# vector-06-easyeda.net
KiCad netlist of a schematic drawn in EasyEDA Pro
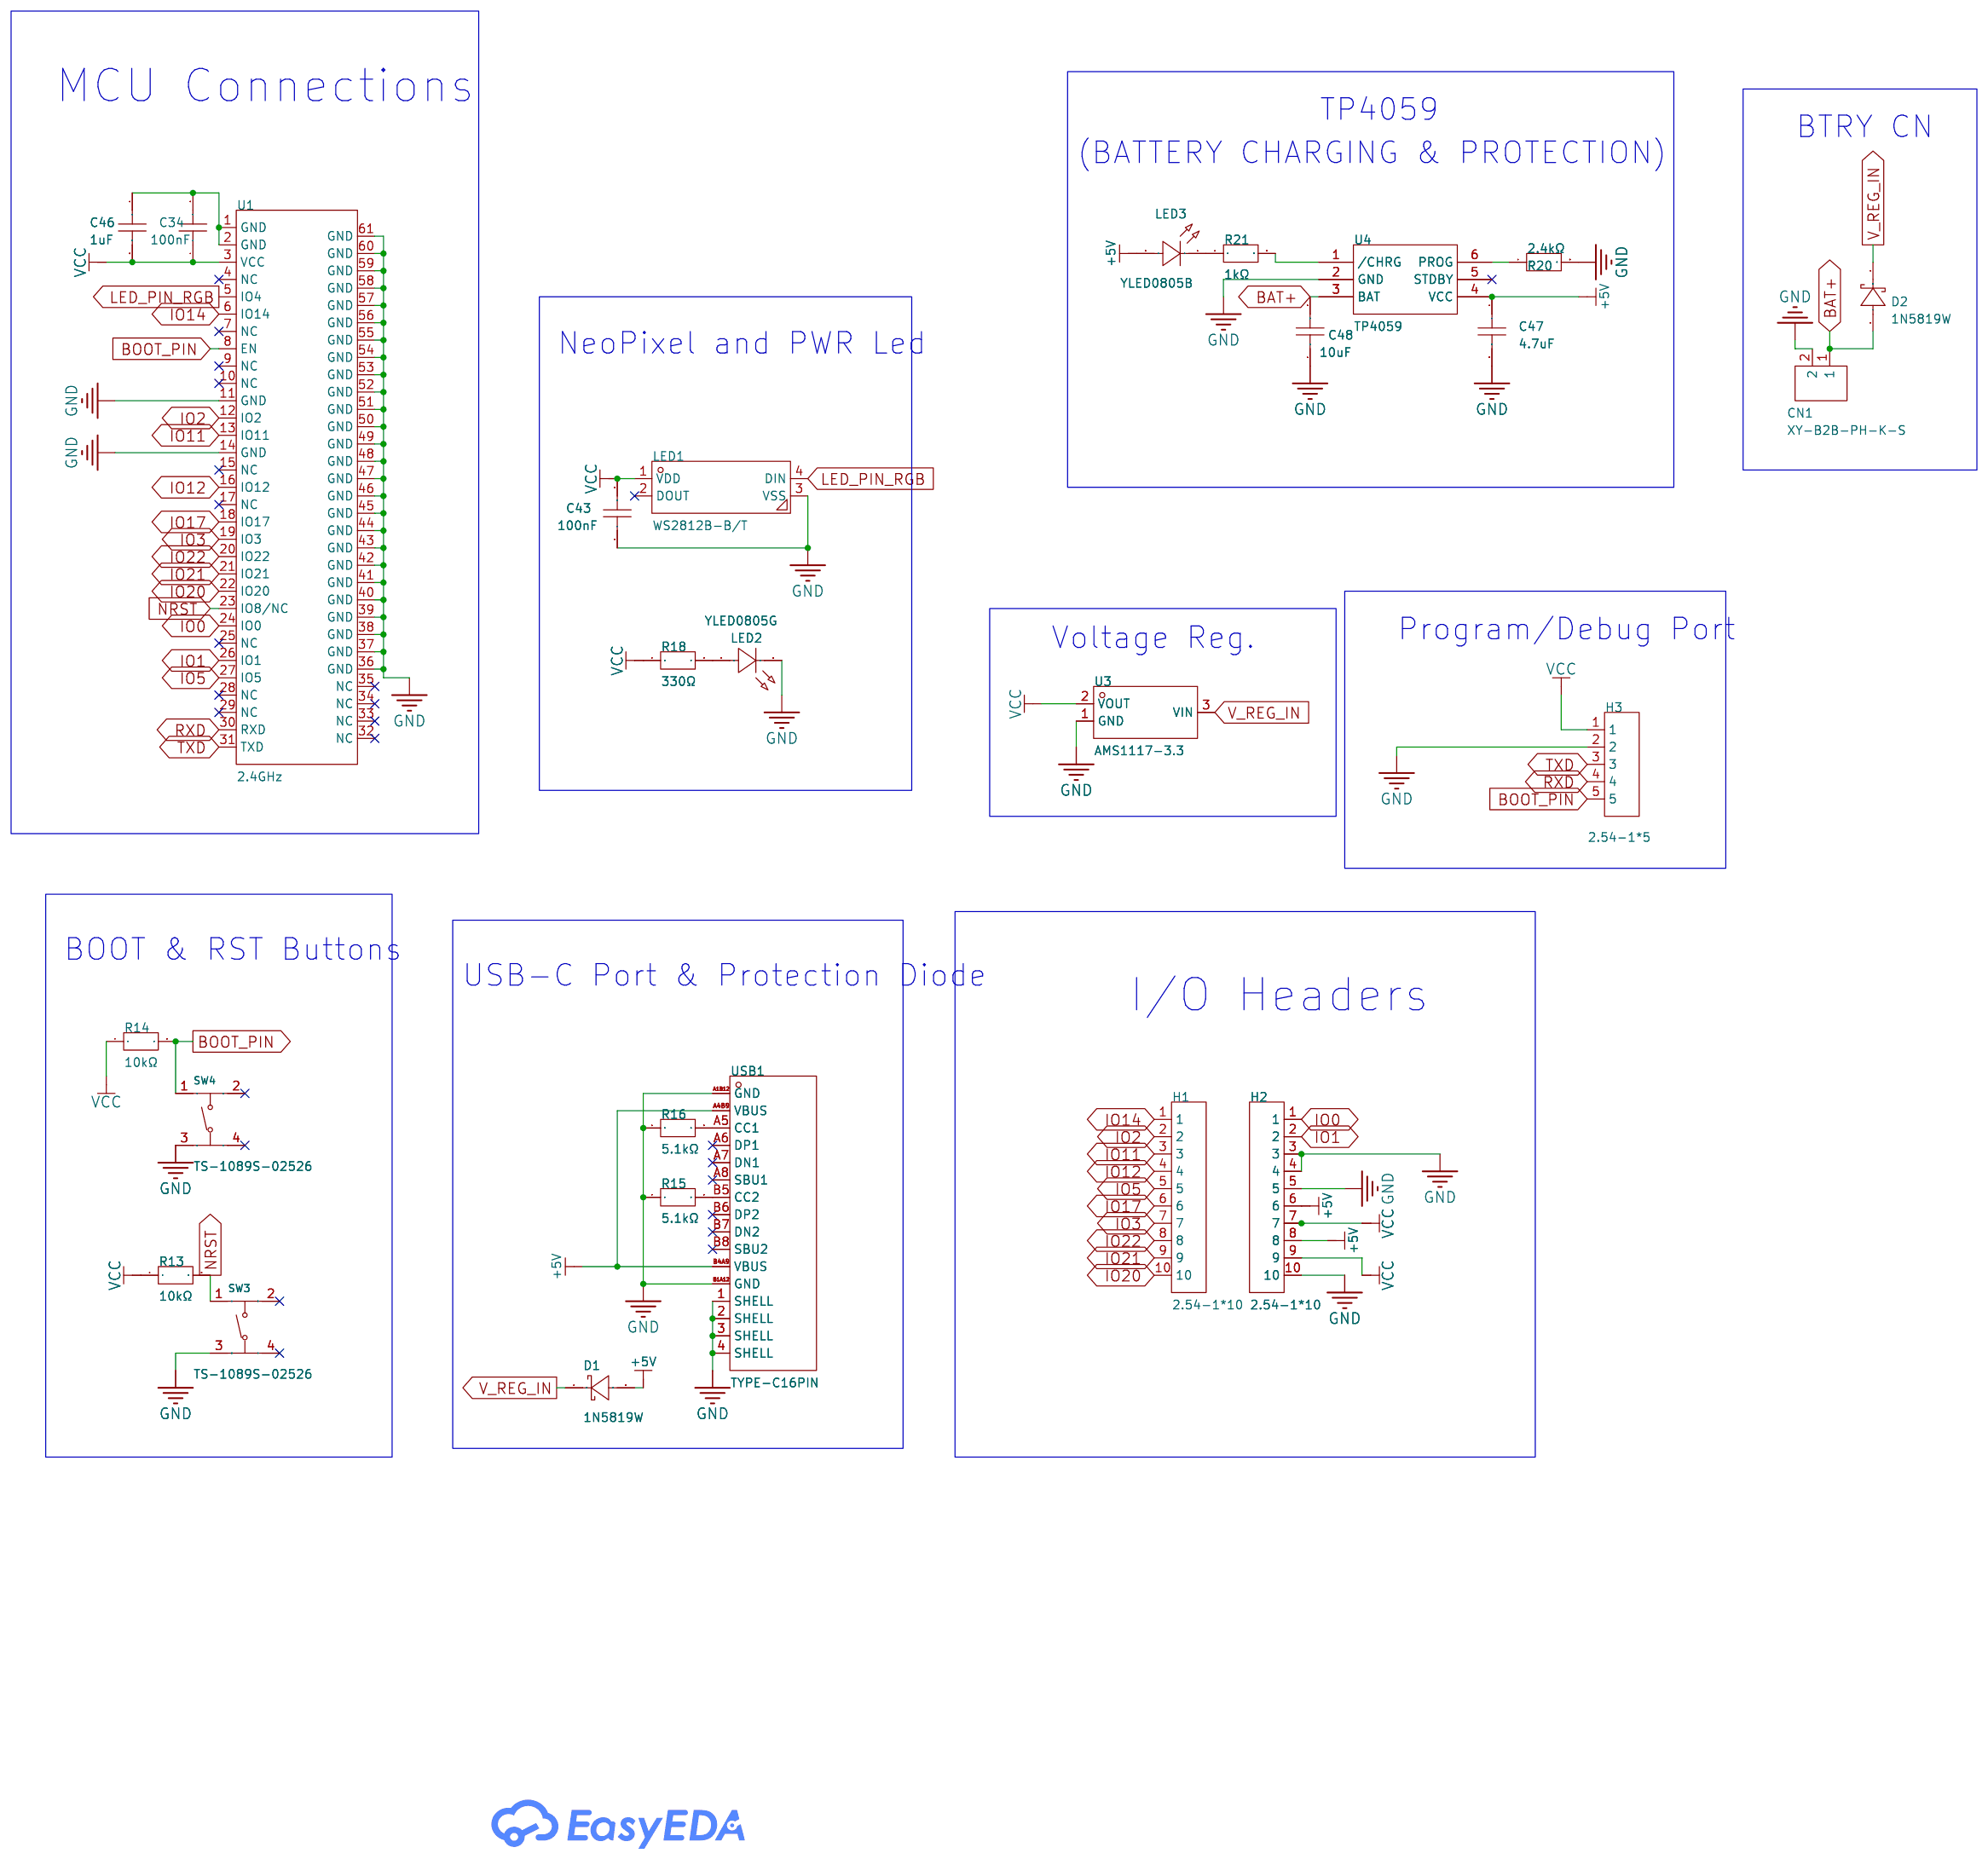
[diagram p0: schematic sheet]

(export (version "E")
  (design (tool "Eeschema 10.0.6"))
  (components
    (comp (ref "C34")
      (value "100nF")
      (footprint "easyedapro:C0603")
      (description "Capacitance:100nF Tolerance:±10% Tolerance:±10% Voltage Rating:50V Temperature Coefficient:X7R")
      (fields
        (field (name "Manufacturer Part") "FCC0603B104K500CT")
        (field (name "Manufacturer") "FOJAN(富捷)")
      )
      (libsource (lib "easyedapro") (part "FCC0603B104K500CT"))
    )
    (comp (ref "C43")
      (value "100nF")
      (footprint "easyedapro:C0603")
      (description "Capacitance:100nF Tolerance:±10% Tolerance:±10% Voltage Rating:50V Temperature Coefficient:X7R")
      (fields
        (field (name "Manufacturer Part") "FCC0603B104K500CT")
        (field (name "Manufacturer") "FOJAN(富捷)")
      )
      (libsource (lib "easyedapro") (part "FCC0603B104K500CT"))
    )
    (comp (ref "C46")
      (value "1uF")
      (footprint "easyedapro:C0603")
      (description "Capacitance:1uF Tolerance:±10% Tolerance:±10% Voltage Rating:50V Temperature Coefficient:X5R")
      (fields
        (field (name "Manufacturer Part") "CGA0603X5R105K500JT")
        (field (name "Manufacturer") "HRE(芯声)")
      )
      (libsource (lib "easyedapro") (part "CGA0603X5R105K500JT"))
    )
    (comp (ref "C47")
      (value "4.7uF")
      (footprint "easyedapro:C0603")
      (description "Capacitance:4.7uF Tolerance:±10% Tolerance:±10% Voltage Rating:16V Temperature Coefficient:X5R")
      (fields
        (field (name "Manufacturer Part") "TCC0603X5R475K160CT")
        (field (name "Manufacturer") "CCTC(三环)")
      )
      (libsource (lib "easyedapro") (part "TCC0603X5R475K160CT"))
    )
    (comp (ref "C48")
      (value "10uF")
      (footprint "easyedapro:C0603")
      (description "Capacitance:10uF Tolerance:±10% Tolerance:±10% Voltage Rating:10V Temperature Coefficient:X5R")
      (fields
        (field (name "Manufacturer Part") "TCC0603X5R106K100CT")
        (field (name "Manufacturer") "CCTC(三环)")
      )
      (libsource (lib "easyedapro") (part "TCC0603X5R106K100CT"))
    )
    (comp (ref "CN1")
      (value "XY-B2B-PH-K-S")
      (footprint "easyedapro:CONN-TH_B2B-PH-K-S")
      (fields (field (name "Manufacturer") "XYECONN(辛译)"))
      (libsource (lib "easyedapro") (part "XY-B2B-PH-K-S"))
    )
    (comp (ref "D1")
      (value "1N5819W")
      (footprint "easyedapro:SOD-123_L2.7-W1.6-LS3.7-RD")
      (fields (field (name "Manufacturer") "GOODWORK(固得沃克)"))
      (libsource (lib "easyedapro") (part "1N5819W_C41431973"))
    )
    (comp (ref "D2")
      (value "1N5819W")
      (footprint "easyedapro:SOD-123_L2.7-W1.6-LS3.7-RD")
      (fields (field (name "Manufacturer") "GOODWORK(固得沃克)"))
      (libsource (lib "easyedapro") (part "1N5819W_C41431973"))
    )
    (comp (ref "H1")
      (value "2.54-1*10")
      (footprint "easyedapro:HDR-TH_10P-P2.54-V-M")
      (fields (field (name "Manufacturer") "ZHOURI(洲日)"))
      (libsource (lib "easyedapro") (part "2.54-1*10"))
    )
    (comp (ref "H2")
      (value "2.54-1*10")
      (footprint "easyedapro:HDR-TH_10P-P2.54-V-M")
      (fields (field (name "Manufacturer") "ZHOURI(洲日)"))
      (libsource (lib "easyedapro") (part "2.54-1*10"))
    )
    (comp (ref "H3")
      (value "2.54-1*5")
      (footprint "easyedapro:HDR-TH_5P-P2.54-V-M")
      (fields (field (name "Manufacturer") "ZHOURI(洲日)"))
      (libsource (lib "easyedapro") (part "2.54-1*5"))
    )
    (comp (ref "LED1")
      (value "WS2812B-B/T")
      (footprint "easyedapro:LED-SMD_4P-L5.0-W5.0-TL_WS2812B-B")
      (fields (field (name "Manufacturer") "worldsemi"))
      (libsource (lib "easyedapro") (part "WS2812B-B/W"))
    )
    (comp (ref "LED2")
      (value "YLED0805G")
      (footprint "easyedapro:LED0805-FD-GREEN")
      (fields (field (name "Manufacturer") "YONGYUTAI(永裕泰)"))
      (libsource (lib "easyedapro") (part "YLED0805G"))
    )
    (comp (ref "LED3")
      (value "YLED0805B")
      (footprint "easyedapro:LED0805-RD")
      (fields (field (name "Manufacturer") "YONGYUTAI(永裕泰)"))
      (libsource (lib "easyedapro") (part "YLED0805B"))
    )
    (comp (ref "R13")
      (value "10kΩ")
      (footprint "easyedapro:R0603")
      (fields (field (name "Manufacturer Part") "FRC0603J103 TS") (field (name "Manufacturer") "FOJAN(富捷)"))
      (libsource (lib "easyedapro") (part "FRC0603J103TS"))
    )
    (comp (ref "R14")
      (value "10kΩ")
      (footprint "easyedapro:R0603")
      (fields (field (name "Manufacturer Part") "FRC0603J103 TS") (field (name "Manufacturer") "FOJAN(富捷)"))
      (libsource (lib "easyedapro") (part "FRC0603J103TS"))
    )
    (comp (ref "R15")
      (value "5.1kΩ")
      (footprint "easyedapro:R0603")
      (fields (field (name "Manufacturer Part") "FRC0603F5101TS") (field (name "Manufacturer") "FOJAN(富捷)"))
      (libsource (lib "easyedapro") (part "FRC0603F5101TS"))
    )
    (comp (ref "R16")
      (value "5.1kΩ")
      (footprint "easyedapro:R0603")
      (fields (field (name "Manufacturer Part") "FRC0603F5101TS") (field (name "Manufacturer") "FOJAN(富捷)"))
      (libsource (lib "easyedapro") (part "FRC0603F5101TS"))
    )
    (comp (ref "R18")
      (value "330Ω")
      (footprint "easyedapro:R0603")
      (fields (field (name "Manufacturer Part") "FRC0603J331 TS") (field (name "Manufacturer") "FOJAN(富捷)"))
      (libsource (lib "easyedapro") (part "FRC0603J331 TS"))
    )
    (comp (ref "R20")
      (value "2.4kΩ")
      (footprint "easyedapro:R0603")
      (fields (field (name "Manufacturer Part") "FRC0603F2401TS") (field (name "Manufacturer") "FOJAN(富捷)"))
      (libsource (lib "easyedapro") (part "FRC0603F2401TS"))
    )
    (comp (ref "R21")
      (value "1kΩ")
      (footprint "easyedapro:R0603")
      (fields (field (name "Manufacturer Part") "FRC0603J102 TS") (field (name "Manufacturer") "FOJAN(富捷)"))
      (libsource (lib "easyedapro") (part "FRC0603J102 TS"))
    )
    (comp (ref "SW3")
      (value "TS-1089S-02526")
      (footprint "easyedapro:SW-SMD_4P-L4.2-W3.3-P2.15-LS5.1")
      (fields (field (name "Manufacturer") "XUNPU(讯普)"))
      (libsource (lib "easyedapro") (part "TS-1089S-02526"))
    )
    (comp (ref "SW4")
      (value "TS-1089S-02526")
      (footprint "easyedapro:SW-SMD_4P-L4.2-W3.3-P2.15-LS5.1")
      (fields (field (name "Manufacturer") "XUNPU(讯普)"))
      (libsource (lib "easyedapro") (part "TS-1089S-02526"))
    )
    (comp (ref "U1")
      (value "2.4GHz")
      (footprint "easyedapro:WIFIM-SMD_61P-L13.2-W12.5-P0.80")
      (fields
        (field (name "Manufacturer Part") "Ai-WB2-M1-I")
        (field (name "Manufacturer") "Ai-Thinker(安信可)")
      )
      (libsource (lib "easyedapro") (part "AI-WB2-M1-I"))
    )
    (comp (ref "U3")
      (value "AMS1117-3.3")
      (footprint "easyedapro:SOT-223-3_L6.5-W3.4-P2.30-LS7.0-BR-1")
      (fields (field (name "Manufacturer") "晶扬电子"))
      (libsource (lib "easyedapro") (part "AMS1117-3.3_C22459274"))
    )
    (comp (ref "U4")
      (value "TP4059")
      (footprint "easyedapro:SOT-23-6_L2.9-W1.6-P0.95-LS2.8-BR")
      (fields (field (name "Manufacturer") "TOPPOWER(南京拓微)"))
      (libsource (lib "easyedapro") (part "TP4059"))
    )
    (comp (ref "USB1")
      (value "TYPE-C16PIN")
      (footprint "easyedapro:USB-C-SMD_TYPE-C16PIN")
      (fields (field (name "Manufacturer") "SHOU HAN(首韩)"))
      (libsource (lib "easyedapro") (part "TYPE-C16PIN"))
    )
  )
  (nets
    (net (code "1") (name "+5V") (class "Default")
      (node (ref "C47") (pin "1") (pinfunction "1_1") (pintype "unspecified"))
      (node (ref "D1") (pin "2") (pinfunction "A_2") (pintype "unspecified"))
      (node (ref "H2") (pin "6") (pinfunction "6_6") (pintype "unspecified"))
      (node (ref "H2") (pin "8") (pinfunction "8_8") (pintype "unspecified"))
      (node (ref "LED3") (pin "2") (pinfunction "A_2") (pintype "unspecified"))
      (node (ref "U4") (pin "4") (pinfunction "VCC_4") (pintype "unspecified"))
      (node (ref "USB1") (pin "A4B9") (pinfunction "VBUS_A4B9") (pintype "unspecified"))
      (node (ref "USB1") (pin "B4A9") (pinfunction "VBUS_B4A9") (pintype "unspecified"))
    )
    (net (code "2") (name "BAT+") (class "Default")
      (node (ref "C48") (pin "2") (pinfunction "2_2") (pintype "unspecified"))
      (node (ref "CN1") (pin "1") (pinfunction "1_1") (pintype "unspecified"))
      (node (ref "D2") (pin "2") (pinfunction "A_2") (pintype "unspecified"))
      (node (ref "U4") (pin "3") (pinfunction "BAT_3") (pintype "unspecified"))
    )
    (net (code "3") (name "BOOT_PIN") (class "Default")
      (node (ref "H3") (pin "5") (pinfunction "5_5") (pintype "unspecified"))
      (node (ref "R14") (pin "2") (pinfunction "2_2") (pintype "unspecified"))
      (node (ref "SW4") (pin "1") (pinfunction "1_1") (pintype "input"))
      (node (ref "U1") (pin "8") (pinfunction "EN_8") (pintype "unspecified"))
    )
    (net (code "4") (name "GND") (class "Default")
      (node (ref "C43") (pin "1") (pinfunction "1_1") (pintype "unspecified"))
      (node (ref "C47") (pin "2") (pinfunction "2_2") (pintype "unspecified"))
      (node (ref "C48") (pin "1") (pinfunction "1_1") (pintype "unspecified"))
      (node (ref "CN1") (pin "2") (pinfunction "2_2") (pintype "unspecified"))
      (node (ref "H2") (pin "10") (pinfunction "10_10") (pintype "unspecified"))
      (node (ref "H2") (pin "3") (pinfunction "3_3") (pintype "unspecified"))
      (node (ref "H2") (pin "4") (pinfunction "4_4") (pintype "unspecified"))
      (node (ref "H2") (pin "5") (pinfunction "5_5") (pintype "unspecified"))
      (node (ref "H3") (pin "2") (pinfunction "2_2") (pintype "unspecified"))
      (node (ref "LED1") (pin "3") (pinfunction "VSS_3") (pintype "unspecified"))
      (node (ref "LED2") (pin "2") (pinfunction "K_2") (pintype "unspecified"))
      (node (ref "R15") (pin "1") (pinfunction "1_1") (pintype "unspecified"))
      (node (ref "R16") (pin "1") (pinfunction "1_1") (pintype "unspecified"))
      (node (ref "R20") (pin "2") (pinfunction "2_2") (pintype "unspecified"))
      (node (ref "SW3") (pin "3") (pinfunction "3_3") (pintype "input"))
      (node (ref "SW4") (pin "3") (pinfunction "3_3") (pintype "input"))
      (node (ref "U1") (pin "11") (pinfunction "GND_11") (pintype "unspecified"))
      (node (ref "U1") (pin "14") (pinfunction "GND_14") (pintype "unspecified"))
      (node (ref "U1") (pin "36") (pinfunction "GND_36") (pintype "unspecified"))
      (node (ref "U1") (pin "37") (pinfunction "GND_37") (pintype "unspecified"))
      (node (ref "U1") (pin "38") (pinfunction "GND_38") (pintype "unspecified"))
      (node (ref "U1") (pin "39") (pinfunction "GND_39") (pintype "unspecified"))
      (node (ref "U1") (pin "40") (pinfunction "GND_40") (pintype "unspecified"))
      (node (ref "U1") (pin "41") (pinfunction "GND_41") (pintype "unspecified"))
      (node (ref "U1") (pin "42") (pinfunction "GND_42") (pintype "unspecified"))
      (node (ref "U1") (pin "43") (pinfunction "GND_43") (pintype "unspecified"))
      (node (ref "U1") (pin "44") (pinfunction "GND_44") (pintype "unspecified"))
      (node (ref "U1") (pin "45") (pinfunction "GND_45") (pintype "unspecified"))
      (node (ref "U1") (pin "46") (pinfunction "GND_46") (pintype "unspecified"))
      (node (ref "U1") (pin "47") (pinfunction "GND_47") (pintype "unspecified"))
      (node (ref "U1") (pin "48") (pinfunction "GND_48") (pintype "unspecified"))
      (node (ref "U1") (pin "49") (pinfunction "GND_49") (pintype "unspecified"))
      (node (ref "U1") (pin "50") (pinfunction "GND_50") (pintype "unspecified"))
      (node (ref "U1") (pin "51") (pinfunction "GND_51") (pintype "unspecified"))
      (node (ref "U1") (pin "52") (pinfunction "GND_52") (pintype "unspecified"))
      (node (ref "U1") (pin "53") (pinfunction "GND_53") (pintype "unspecified"))
      (node (ref "U1") (pin "54") (pinfunction "GND_54") (pintype "unspecified"))
      (node (ref "U1") (pin "55") (pinfunction "GND_55") (pintype "unspecified"))
      (node (ref "U1") (pin "56") (pinfunction "GND_56") (pintype "unspecified"))
      (node (ref "U1") (pin "57") (pinfunction "GND_57") (pintype "unspecified"))
      (node (ref "U1") (pin "58") (pinfunction "GND_58") (pintype "unspecified"))
      (node (ref "U1") (pin "59") (pinfunction "GND_59") (pintype "unspecified"))
      (node (ref "U1") (pin "60") (pinfunction "GND_60") (pintype "unspecified"))
      (node (ref "U1") (pin "61") (pinfunction "GND_61") (pintype "unspecified"))
      (node (ref "U3") (pin "1") (pinfunction "GND_1") (pintype "unspecified"))
      (node (ref "U4") (pin "2") (pinfunction "GND_2") (pintype "unspecified"))
      (node (ref "USB1") (pin "1") (pinfunction "SHELL_1") (pintype "unspecified"))
      (node (ref "USB1") (pin "2") (pinfunction "SHELL_2") (pintype "unspecified"))
      (node (ref "USB1") (pin "3") (pinfunction "SHELL_3") (pintype "unspecified"))
      (node (ref "USB1") (pin "4") (pinfunction "SHELL_4") (pintype "unspecified"))
      (node (ref "USB1") (pin "A1B12") (pinfunction "GND_A1B12") (pintype "unspecified"))
      (node (ref "USB1") (pin "B1A12") (pinfunction "GND_B1A12") (pintype "unspecified"))
    )
    (net (code "5") (name "IO0") (class "Default")
      (node (ref "H2") (pin "1") (pinfunction "1_1") (pintype "unspecified"))
      (node (ref "U1") (pin "24") (pinfunction "IO0_24") (pintype "unspecified"))
    )
    (net (code "6") (name "IO1") (class "Default")
      (node (ref "H2") (pin "2") (pinfunction "2_2") (pintype "unspecified"))
      (node (ref "U1") (pin "26") (pinfunction "IO1_26") (pintype "unspecified"))
    )
    (net (code "7") (name "IO2") (class "Default")
      (node (ref "H1") (pin "2") (pinfunction "2_2") (pintype "unspecified"))
      (node (ref "U1") (pin "12") (pinfunction "IO2_12") (pintype "unspecified"))
    )
    (net (code "8") (name "IO3") (class "Default")
      (node (ref "H1") (pin "7") (pinfunction "7_7") (pintype "unspecified"))
      (node (ref "U1") (pin "19") (pinfunction "IO3_19") (pintype "unspecified"))
    )
    (net (code "9") (name "IO5") (class "Default")
      (node (ref "H1") (pin "5") (pinfunction "5_5") (pintype "unspecified"))
      (node (ref "U1") (pin "27") (pinfunction "IO5_27") (pintype "unspecified"))
    )
    (net (code "10") (name "IO11") (class "Default")
      (node (ref "H1") (pin "3") (pinfunction "3_3") (pintype "unspecified"))
      (node (ref "U1") (pin "13") (pinfunction "IO11_13") (pintype "unspecified"))
    )
    (net (code "11") (name "IO12") (class "Default")
      (node (ref "H1") (pin "4") (pinfunction "4_4") (pintype "unspecified"))
      (node (ref "U1") (pin "16") (pinfunction "IO12_16") (pintype "unspecified"))
    )
    (net (code "12") (name "IO14") (class "Default")
      (node (ref "H1") (pin "1") (pinfunction "1_1") (pintype "unspecified"))
      (node (ref "U1") (pin "6") (pinfunction "IO14_6") (pintype "unspecified"))
    )
    (net (code "13") (name "IO17") (class "Default")
      (node (ref "H1") (pin "6") (pinfunction "6_6") (pintype "unspecified"))
      (node (ref "U1") (pin "18") (pinfunction "IO17_18") (pintype "unspecified"))
    )
    (net (code "14") (name "IO20") (class "Default")
      (node (ref "H1") (pin "10") (pinfunction "10_10") (pintype "unspecified"))
      (node (ref "U1") (pin "22") (pinfunction "IO20_22") (pintype "unspecified"))
    )
    (net (code "15") (name "IO21") (class "Default")
      (node (ref "H1") (pin "9") (pinfunction "9_9") (pintype "unspecified"))
      (node (ref "U1") (pin "21") (pinfunction "IO21_21") (pintype "unspecified"))
    )
    (net (code "16") (name "IO22") (class "Default")
      (node (ref "H1") (pin "8") (pinfunction "8_8") (pintype "unspecified"))
      (node (ref "U1") (pin "20") (pinfunction "IO22_20") (pintype "unspecified"))
    )
    (net (code "17") (name "LED_PIN_RGB") (class "Default")
      (node (ref "LED1") (pin "4") (pinfunction "DIN_4") (pintype "unspecified"))
      (node (ref "U1") (pin "5") (pinfunction "IO4_5") (pintype "unspecified"))
    )
    (net (code "18") (name "NRST") (class "Default")
      (node (ref "R13") (pin "2") (pinfunction "2_2") (pintype "unspecified"))
      (node (ref "SW3") (pin "1") (pinfunction "1_1") (pintype "input"))
      (node (ref "U1") (pin "23") (pinfunction "IO8/NC_23") (pintype "unspecified"))
    )
    (net (code "19") (name "Net-(C34-Pad2)") (class "Default")
      (node (ref "C34") (pin "2") (pinfunction "2_2") (pintype "unspecified"))
      (node (ref "C46") (pin "1") (pinfunction "1_1") (pintype "unspecified"))
      (node (ref "U1") (pin "1") (pinfunction "GND_1") (pintype "unspecified"))
      (node (ref "U1") (pin "2") (pinfunction "GND_2") (pintype "unspecified"))
    )
    (net (code "20") (name "Net-(LED2-A)") (class "Default")
      (node (ref "LED2") (pin "1") (pinfunction "A_1") (pintype "unspecified"))
      (node (ref "R18") (pin "2") (pinfunction "2_2") (pintype "unspecified"))
    )
    (net (code "21") (name "Net-(LED3-K)") (class "Default")
      (node (ref "LED3") (pin "1") (pinfunction "K_1") (pintype "unspecified"))
      (node (ref "R21") (pin "1") (pinfunction "1_1") (pintype "unspecified"))
    )
    (net (code "22") (name "Net-(U4-PROG)") (class "Default")
      (node (ref "R20") (pin "1") (pinfunction "1_1") (pintype "unspecified"))
      (node (ref "U4") (pin "6") (pinfunction "PROG_6") (pintype "unspecified"))
    )
    (net (code "23") (name "Net-(U4-{slash}CHRG)") (class "Default")
      (node (ref "R21") (pin "2") (pinfunction "2_2") (pintype "unspecified"))
      (node (ref "U4") (pin "1") (pinfunction "/CHRG_1") (pintype "unspecified"))
    )
    (net (code "24") (name "Net-(USB1-CC1)") (class "Default")
      (node (ref "R16") (pin "2") (pinfunction "2_2") (pintype "unspecified"))
      (node (ref "USB1") (pin "A5") (pinfunction "CC1_A5") (pintype "unspecified"))
    )
    (net (code "25") (name "Net-(USB1-CC2)") (class "Default")
      (node (ref "R15") (pin "2") (pinfunction "2_2") (pintype "unspecified"))
      (node (ref "USB1") (pin "B5") (pinfunction "CC2_B5") (pintype "unspecified"))
    )
    (net (code "26") (name "RXD") (class "Default")
      (node (ref "H3") (pin "4") (pinfunction "4_4") (pintype "unspecified"))
      (node (ref "U1") (pin "30") (pinfunction "RXD_30") (pintype "unspecified"))
    )
    (net (code "27") (name "TXD") (class "Default")
      (node (ref "H3") (pin "3") (pinfunction "3_3") (pintype "unspecified"))
      (node (ref "U1") (pin "31") (pinfunction "TXD_31") (pintype "unspecified"))
    )
    (net (code "28") (name "VCC") (class "Default")
      (node (ref "C34") (pin "1") (pinfunction "1_1") (pintype "unspecified"))
      (node (ref "C43") (pin "2") (pinfunction "2_2") (pintype "unspecified"))
      (node (ref "C46") (pin "2") (pinfunction "2_2") (pintype "unspecified"))
      (node (ref "H2") (pin "7") (pinfunction "7_7") (pintype "unspecified"))
      (node (ref "H2") (pin "9") (pinfunction "9_9") (pintype "unspecified"))
      (node (ref "H3") (pin "1") (pinfunction "1_1") (pintype "unspecified"))
      (node (ref "LED1") (pin "1") (pinfunction "VDD_1") (pintype "unspecified"))
      (node (ref "R13") (pin "1") (pinfunction "1_1") (pintype "unspecified"))
      (node (ref "R14") (pin "1") (pinfunction "1_1") (pintype "unspecified"))
      (node (ref "R18") (pin "1") (pinfunction "1_1") (pintype "unspecified"))
      (node (ref "U1") (pin "3") (pinfunction "VCC_3") (pintype "unspecified"))
      (node (ref "U3") (pin "2") (pinfunction "VOUT_2") (pintype "unspecified"))
    )
    (net (code "29") (name "V_REG_IN") (class "Default")
      (node (ref "D1") (pin "1") (pinfunction "C_1") (pintype "unspecified"))
      (node (ref "D2") (pin "1") (pinfunction "C_1") (pintype "unspecified"))
      (node (ref "U3") (pin "3") (pinfunction "VIN_3") (pintype "unspecified"))
    )
    (net (code "30") (name "unconnected-(LED1-DOUT-Pad2)") (class "Default")
      (node (ref "LED1") (pin "2") (pinfunction "DOUT_2") (pintype "unspecified+no_connect"))
    )
    (net (code "31") (name "unconnected-(SW3-Pad2)") (class "Default")
      (node (ref "SW3") (pin "2") (pinfunction "2_2") (pintype "input+no_connect"))
    )
    (net (code "32") (name "unconnected-(SW3-Pad4)") (class "Default")
      (node (ref "SW3") (pin "4") (pinfunction "4_4") (pintype "input+no_connect"))
    )
    (net (code "33") (name "unconnected-(SW4-Pad2)") (class "Default")
      (node (ref "SW4") (pin "2") (pinfunction "2_2") (pintype "input+no_connect"))
    )
    (net (code "34") (name "unconnected-(SW4-Pad4)") (class "Default")
      (node (ref "SW4") (pin "4") (pinfunction "4_4") (pintype "input+no_connect"))
    )
    (net (code "35") (name "unconnected-(U1-NC-Pad4)") (class "Default")
      (node (ref "U1") (pin "4") (pinfunction "NC_4") (pintype "unspecified+no_connect"))
    )
    (net (code "36") (name "unconnected-(U1-NC-Pad7)") (class "Default")
      (node (ref "U1") (pin "7") (pinfunction "NC_7") (pintype "unspecified+no_connect"))
    )
    (net (code "37") (name "unconnected-(U1-NC-Pad9)") (class "Default")
      (node (ref "U1") (pin "9") (pinfunction "NC_9") (pintype "unspecified+no_connect"))
    )
    (net (code "38") (name "unconnected-(U1-NC-Pad10)") (class "Default")
      (node (ref "U1") (pin "10") (pinfunction "NC_10") (pintype "unspecified+no_connect"))
    )
    (net (code "39") (name "unconnected-(U1-NC-Pad15)") (class "Default")
      (node (ref "U1") (pin "15") (pinfunction "NC_15") (pintype "unspecified+no_connect"))
    )
    (net (code "40") (name "unconnected-(U1-NC-Pad17)") (class "Default")
      (node (ref "U1") (pin "17") (pinfunction "NC_17") (pintype "unspecified+no_connect"))
    )
    (net (code "41") (name "unconnected-(U1-NC-Pad25)") (class "Default")
      (node (ref "U1") (pin "25") (pinfunction "NC_25") (pintype "unspecified+no_connect"))
    )
    (net (code "42") (name "unconnected-(U1-NC-Pad28)") (class "Default")
      (node (ref "U1") (pin "28") (pinfunction "NC_28") (pintype "unspecified+no_connect"))
    )
    (net (code "43") (name "unconnected-(U1-NC-Pad29)") (class "Default")
      (node (ref "U1") (pin "29") (pinfunction "NC_29") (pintype "unspecified+no_connect"))
    )
    (net (code "44") (name "unconnected-(U1-NC-Pad32)") (class "Default")
      (node (ref "U1") (pin "32") (pinfunction "NC_32") (pintype "unspecified+no_connect"))
    )
    (net (code "45") (name "unconnected-(U1-NC-Pad33)") (class "Default")
      (node (ref "U1") (pin "33") (pinfunction "NC_33") (pintype "unspecified+no_connect"))
    )
    (net (code "46") (name "unconnected-(U1-NC-Pad34)") (class "Default")
      (node (ref "U1") (pin "34") (pinfunction "NC_34") (pintype "unspecified+no_connect"))
    )
    (net (code "47") (name "unconnected-(U1-NC-Pad35)") (class "Default")
      (node (ref "U1") (pin "35") (pinfunction "NC_35") (pintype "unspecified+no_connect"))
    )
    (net (code "48") (name "unconnected-(U4-STDBY-Pad5)") (class "Default")
      (node (ref "U4") (pin "5") (pinfunction "STDBY_5") (pintype "unspecified+no_connect"))
    )
    (net (code "49") (name "unconnected-(USB1-DN1-PadA7)") (class "Default")
      (node (ref "USB1") (pin "A7") (pinfunction "DN1_A7") (pintype "unspecified+no_connect"))
    )
    (net (code "50") (name "unconnected-(USB1-DN2-PadB7)") (class "Default")
      (node (ref "USB1") (pin "B7") (pinfunction "DN2_B7") (pintype "unspecified+no_connect"))
    )
    (net (code "51") (name "unconnected-(USB1-DP1-PadA6)") (class "Default")
      (node (ref "USB1") (pin "A6") (pinfunction "DP1_A6") (pintype "unspecified+no_connect"))
    )
    (net (code "52") (name "unconnected-(USB1-DP2-PadB6)") (class "Default")
      (node (ref "USB1") (pin "B6") (pinfunction "DP2_B6") (pintype "unspecified+no_connect"))
    )
    (net (code "53") (name "unconnected-(USB1-SBU1-PadA8)") (class "Default")
      (node (ref "USB1") (pin "A8") (pinfunction "SBU1_A8") (pintype "unspecified+no_connect"))
    )
    (net (code "54") (name "unconnected-(USB1-SBU2-PadB8)") (class "Default")
      (node (ref "USB1") (pin "B8") (pinfunction "SBU2_B8") (pintype "unspecified+no_connect"))
    )
  )
)
